# heater-v1.net
KiCad netlist of a schematic drawn in EAGLE
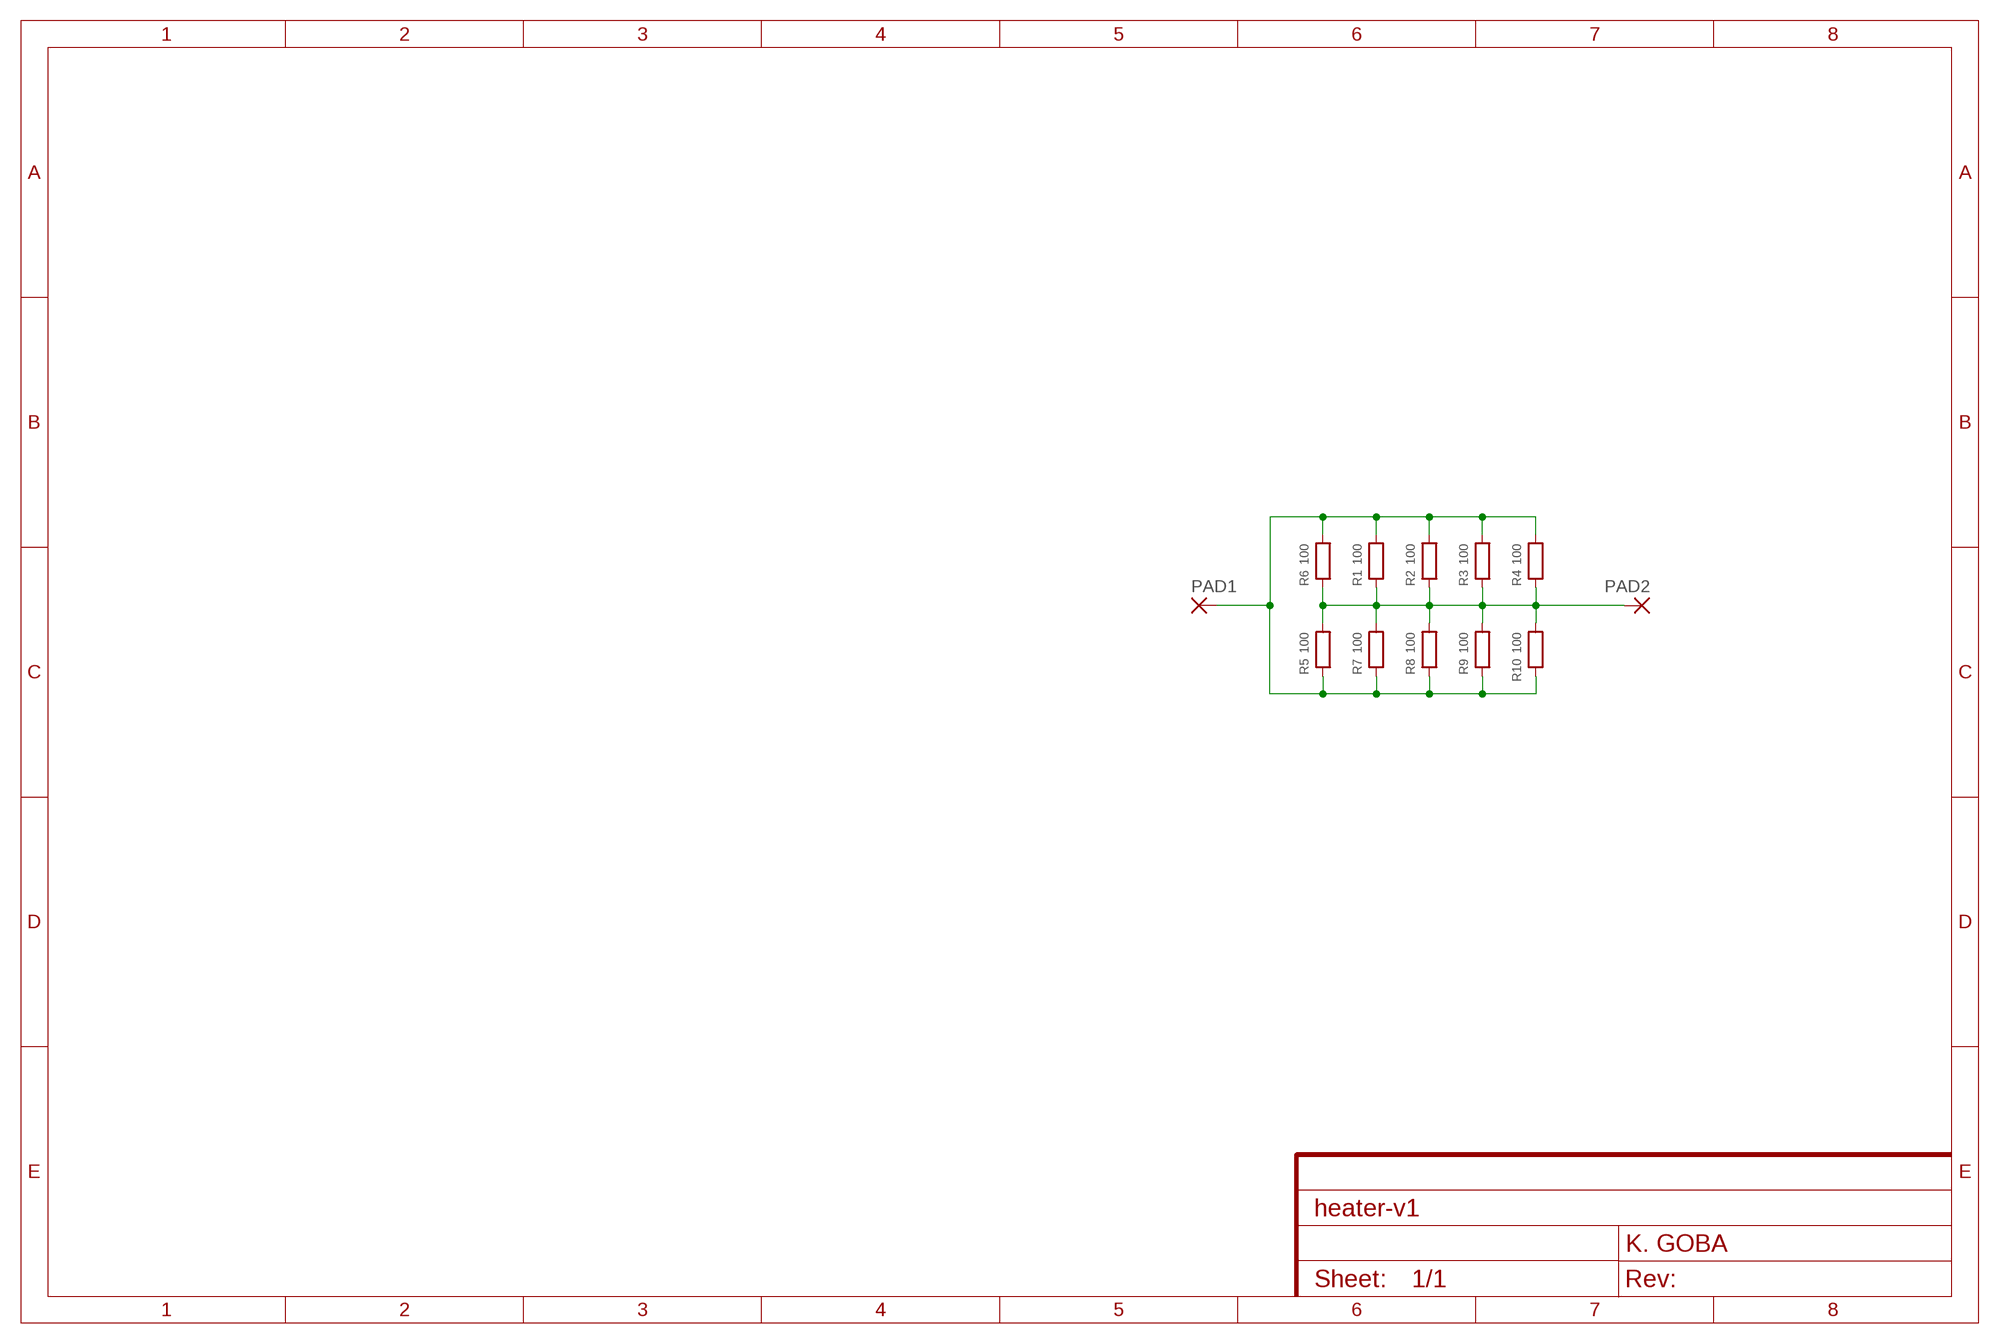
[diagram p0: schematic, sheet 1]

(export (version "E")
  (design (tool "Eeschema 10.0.6"))
  (components
    (comp (ref "PAD1")
      (value "1,6/0,8")
      (footprint "eagle-import:1,6_0,8")
      (libsource (lib "eagle-import") (part "1,6/0,8"))
    )
    (comp (ref "PAD2")
      (value "1,6/0,8")
      (footprint "eagle-import:1,6_0,8")
      (libsource (lib "eagle-import") (part "1,6/0,8"))
    )
    (comp (ref "R1")
      (value "100")
      (footprint "eagle-import:R1206")
      (libsource (lib "eagle-import") (part "RESISTOR-1206"))
    )
    (comp (ref "R2")
      (value "100")
      (footprint "eagle-import:R1206")
      (libsource (lib "eagle-import") (part "RESISTOR-1206"))
    )
    (comp (ref "R3")
      (value "100")
      (footprint "eagle-import:R1206")
      (libsource (lib "eagle-import") (part "RESISTOR-1206"))
    )
    (comp (ref "R4")
      (value "100")
      (footprint "eagle-import:R1206")
      (libsource (lib "eagle-import") (part "RESISTOR-1206"))
    )
    (comp (ref "R5")
      (value "100")
      (footprint "eagle-import:R1206")
      (libsource (lib "eagle-import") (part "RESISTOR-1206"))
    )
    (comp (ref "R6")
      (value "100")
      (footprint "eagle-import:R1206")
      (libsource (lib "eagle-import") (part "RESISTOR-1206"))
    )
    (comp (ref "R7")
      (value "100")
      (footprint "eagle-import:R1206")
      (libsource (lib "eagle-import") (part "RESISTOR-1206"))
    )
    (comp (ref "R8")
      (value "100")
      (footprint "eagle-import:R1206")
      (libsource (lib "eagle-import") (part "RESISTOR-1206"))
    )
    (comp (ref "R9")
      (value "100")
      (footprint "eagle-import:R1206")
      (libsource (lib "eagle-import") (part "RESISTOR-1206"))
    )
    (comp (ref "R10")
      (value "100")
      (footprint "eagle-import:R1206")
      (libsource (lib "eagle-import") (part "RESISTOR-1206"))
    )
  )
  (nets
    (net (code "1") (name "Net-(PAD1-P)") (class "Default")
      (node (ref "PAD1") (pin "1") (pinfunction "P_1") (pintype "passive"))
      (node (ref "R1") (pin "2") (pinfunction "2_2") (pintype "passive"))
      (node (ref "R10") (pin "1") (pinfunction "1_1") (pintype "passive"))
      (node (ref "R2") (pin "2") (pinfunction "2_2") (pintype "passive"))
      (node (ref "R3") (pin "2") (pinfunction "2_2") (pintype "passive"))
      (node (ref "R4") (pin "2") (pinfunction "2_2") (pintype "passive"))
      (node (ref "R5") (pin "1") (pinfunction "1_1") (pintype "passive"))
      (node (ref "R6") (pin "2") (pinfunction "2_2") (pintype "passive"))
      (node (ref "R7") (pin "1") (pinfunction "1_1") (pintype "passive"))
      (node (ref "R8") (pin "1") (pinfunction "1_1") (pintype "passive"))
      (node (ref "R9") (pin "1") (pinfunction "1_1") (pintype "passive"))
    )
    (net (code "2") (name "Net-(PAD2-P)") (class "Default")
      (node (ref "PAD2") (pin "1") (pinfunction "P_1") (pintype "passive"))
      (node (ref "R1") (pin "1") (pinfunction "1_1") (pintype "passive"))
      (node (ref "R10") (pin "2") (pinfunction "2_2") (pintype "passive"))
      (node (ref "R2") (pin "1") (pinfunction "1_1") (pintype "passive"))
      (node (ref "R3") (pin "1") (pinfunction "1_1") (pintype "passive"))
      (node (ref "R4") (pin "1") (pinfunction "1_1") (pintype "passive"))
      (node (ref "R5") (pin "2") (pinfunction "2_2") (pintype "passive"))
      (node (ref "R6") (pin "1") (pinfunction "1_1") (pintype "passive"))
      (node (ref "R7") (pin "2") (pinfunction "2_2") (pintype "passive"))
      (node (ref "R8") (pin "2") (pinfunction "2_2") (pintype "passive"))
      (node (ref "R9") (pin "2") (pinfunction "2_2") (pintype "passive"))
    )
  )
)
